# untitled.net
KiCad netlist of a schematic drawn in EAGLE
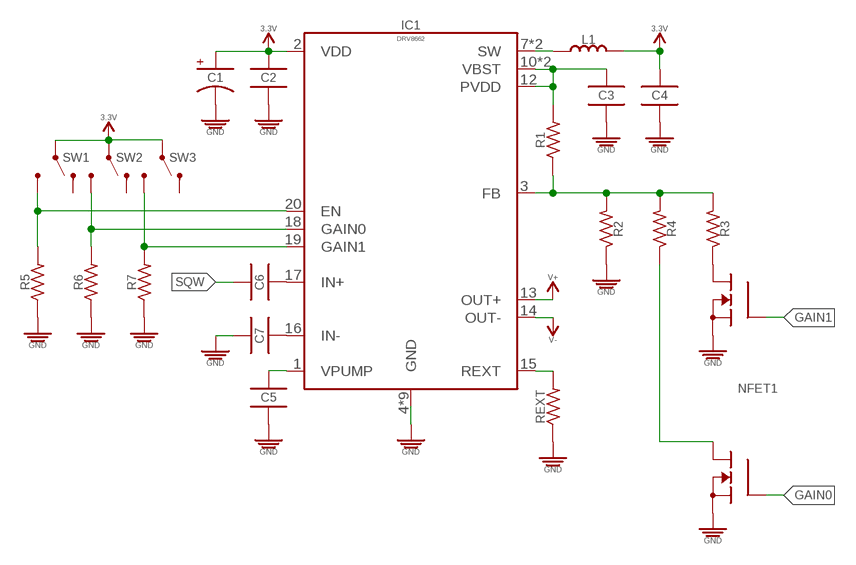
[diagram p0: schematic, sheet 1]

(export (version "E")
  (design (tool "Eeschema 10.0.6"))
  (components
    (comp (ref "C1")
      (value "100uF/10V")
      (footprint "eagle-import:CAPCP3216X160")
      (fields (field (name "MFR") "AVX Corporation") (field (name "MPN") "TLJA107M010R1400"))
      (libsource (lib "eagle-import") (part "100UF-POLARIZED_TANT_SMD-1206_10V-20%"))
    )
    (comp (ref "C2")
      (value "0.1uF/50V")
      (footprint "eagle-import:CAPC1005X55_SMD-0402")
      (fields (field (name "MFR") "TDK Corporation") (field (name "MPN") "C1005X7R1H104K050BE"))
      (libsource (lib "eagle-import") (part "0.1UF_SMD-0402_50V-10%"))
    )
    (comp (ref "C3")
      (value "0.1uF/250V/0805")
      (footprint "eagle-import:CAPC2012X95_SMD-0805")
      (fields (field (name "MFR") "TDK Corporation") (field (name "MPN") "C2012X7T2E104M125AE"))
      (libsource (lib "eagle-import") (part "0.1UF_SMD-0805_250V-10%"))
    )
    (comp (ref "C4")
      (value "0.1uF/50V")
      (footprint "eagle-import:CAPC1608X95")
      (fields (field (name "MFR") "TDK Corporation") (field (name "MPN") "CGA3E3X8R1H104K080AB"))
      (libsource (lib "eagle-import") (part "0.1UF_SMD-0603_50V-20%"))
    )
    (comp (ref "C5")
      (value "0.1uF/50V")
      (footprint "eagle-import:CAPC1005X55_SMD-0402")
      (fields (field (name "MFR") "TDK Corporation") (field (name "MPN") "C1005X7R1H104K050BE"))
      (libsource (lib "eagle-import") (part "0.1UF_SMD-0402_50V-10%"))
    )
    (comp (ref "C6")
      (value "0.1uF/50V")
      (footprint "eagle-import:CAPC1005X55_SMD-0402")
      (fields (field (name "MFR") "TDK Corporation") (field (name "MPN") "C1005X7R1H104K050BE"))
      (libsource (lib "eagle-import") (part "0.1UF_SMD-0402_50V-10%"))
    )
    (comp (ref "C7")
      (value "0.1uF/50V")
      (footprint "eagle-import:CAPC1005X55_SMD-0402")
      (fields (field (name "MFR") "TDK Corporation") (field (name "MPN") "C1005X7R1H104K050BE"))
      (libsource (lib "eagle-import") (part "0.1UF_SMD-0402_50V-10%"))
    )
    (comp (ref "IC1")
      (value "DRV8662")
      (footprint "eagle-import:QFN50P400X400X100-21T270")
      (fields (field (name "MFR") "Texas Instruments") (field (name "MPN") "DRV8662RGPR"))
      (libsource (lib "eagle-import") (part "DRV8662_PIEZO_HAPTICS_DRIVER_QFN-20-EP"))
    )
    (comp (ref "L1")
      (value "4.7uH/2A/1008")
      (footprint "eagle-import:INDC2520X100")
      (fields
        (field (name "MFR") "Murata Electronics North America")
        (field (name "MPN") "DFE252012P-4R7M=P2")
      )
      (libsource (lib "eagle-import") (part "4.7UH_SMD-1008_2A-0.200OHM-20%"))
    )
    (comp (ref "NFET1")
      (value "2N7002DW")
      (footprint "eagle-import:SOT65P230X110-6")
      (fields (field (name "MFR") "Micro Commercial Co") (field (name "MPN") "2N7002DW-TP"))
      (libsource (lib "eagle-import") (part "MOSFET_N-CHANNEL_2-ARRAY_2N7002DW_115MA-60V"))
    )
    (comp (ref "R1")
      (value "768K")
      (footprint "eagle-import:RESC1005X35_SMD-0402")
      (fields (field (name "MFR") "Yageo") (field (name "MPN") "RC0402FR-07768KL"))
      (libsource (lib "eagle-import") (part "768KΩ_SMD-0402_1/16W-1%"))
    )
    (comp (ref "R2")
      (value "115K")
      (footprint "eagle-import:RESC1005X35_SMD-0402")
      (fields (field (name "MFR") "Yageo") (field (name "MPN") "RC0402FR-0735K7L"))
      (libsource (lib "eagle-import") (part "35.7KΩ_SMD-0402_1/16W-1%"))
    )
    (comp (ref "R3")
      (value "220K")
      (footprint "eagle-import:RESC1005X35_SMD-0402")
      (fields (field (name "MFR") "Yageo") (field (name "MPN") "RC0402FR-0720KL"))
      (libsource (lib "eagle-import") (part "20KΩ_SMD-0402_1/16W-1%"))
    )
    (comp (ref "R4")
      (value "100K")
      (footprint "eagle-import:RESC1005X35_SMD-0402")
      (fields (field (name "MFR") "Yageo") (field (name "MPN") "RC0402FR-0741K2L"))
      (libsource (lib "eagle-import") (part "41.2KΩ_SMD-0402_1/16W-1%"))
    )
    (comp (ref "R5")
      (value "10K")
      (footprint "eagle-import:RESC1005X35_SMD-0402")
      (fields (field (name "MFR") "Yageo") (field (name "MPN") "RC0402JR-0710KP"))
      (libsource (lib "eagle-import") (part "10KΩ_SMD-0402_1/16W-5%"))
    )
    (comp (ref "R6")
      (value "10K")
      (footprint "eagle-import:RESC1005X35_SMD-0402")
      (fields (field (name "MFR") "Yageo") (field (name "MPN") "RC0402JR-0710KP"))
      (libsource (lib "eagle-import") (part "10KΩ_SMD-0402_1/16W-5%"))
    )
    (comp (ref "R7")
      (value "10K")
      (footprint "eagle-import:RESC1005X35_SMD-0402")
      (fields (field (name "MFR") "Yageo") (field (name "MPN") "RC0402JR-0710KP"))
      (libsource (lib "eagle-import") (part "10KΩ_SMD-0402_1/16W-5%"))
    )
    (comp (ref "REXT")
      (value "7.5K")
      (footprint "eagle-import:RESC1005X35_SMD-0402")
      (fields (field (name "MFR") "Yageo") (field (name "MPN") "RC0402FR-077K5L"))
      (libsource (lib "eagle-import") (part "7.5KΩ_SMD-0402_1/16W-1%"))
    )
    (comp (ref "SW1")
      (value "300mA/4V")
      (footprint "eagle-import:SW_SLIDE_SPDT_RA_SMD_4V_300MA_6.7L-2.6W")
      (fields
        (field (name "MFR") "APEM Inc.")
        (field (name "MPN") "MA12RTR")
        (field (name "CREATOR") "MrSwirlyEyes")
      )
      (libsource (lib "eagle-import") (part "SWITCH_SPDT_RA_SMD_300MA-4V_6.7L-2.6W"))
    )
    (comp (ref "SW2")
      (value "300mA/4V")
      (footprint "eagle-import:SW_SLIDE_SPDT_RA_SMD_4V_300MA_6.7L-2.6W")
      (fields
        (field (name "MFR") "APEM Inc.")
        (field (name "MPN") "MA12RTR")
        (field (name "CREATOR") "MrSwirlyEyes")
      )
      (libsource (lib "eagle-import") (part "SWITCH_SPDT_RA_SMD_300MA-4V_6.7L-2.6W"))
    )
    (comp (ref "SW3")
      (value "300mA/4V")
      (footprint "eagle-import:SW_SLIDE_SPDT_RA_SMD_4V_300MA_6.7L-2.6W")
      (fields
        (field (name "MFR") "APEM Inc.")
        (field (name "MPN") "MA12RTR")
        (field (name "CREATOR") "MrSwirlyEyes")
      )
      (libsource (lib "eagle-import") (part "SWITCH_SPDT_RA_SMD_300MA-4V_6.7L-2.6W"))
    )
  )
  (nets
    (net (code "1") (name "3.3V") (class "Default")
      (node (ref "C1") (pin "A") (pinfunction "A_A") (pintype "passive"))
      (node (ref "C2") (pin "1") (pinfunction "1_1") (pintype "passive"))
      (node (ref "C4") (pin "1") (pinfunction "1_1") (pintype "passive"))
      (node (ref "IC1") (pin "2") (pinfunction "VDD_2") (pintype "power_in"))
      (node (ref "L1") (pin "2") (pinfunction "2_2") (pintype "passive"))
      (node (ref "SW1") (pin "2") (pinfunction "P_2") (pintype "passive"))
      (node (ref "SW2") (pin "2") (pinfunction "P_2") (pintype "passive"))
      (node (ref "SW3") (pin "2") (pinfunction "P_2") (pintype "passive"))
    )
    (net (code "2") (name "GAIN0") (class "Default")
      (node (ref "IC1") (pin "18") (pinfunction "GAIN0_18") (pintype "input"))
      (node (ref "NFET1") (pin "5") (pinfunction "G2_5") (pintype "passive"))
      (node (ref "R6") (pin "2") (pinfunction "2_2") (pintype "passive"))
      (node (ref "SW2") (pin "3") (pinfunction "S2_3") (pintype "passive"))
    )
    (net (code "3") (name "GAIN1") (class "Default")
      (node (ref "IC1") (pin "19") (pinfunction "GAIN1_19") (pintype "input"))
      (node (ref "NFET1") (pin "2") (pinfunction "G1_2") (pintype "passive"))
      (node (ref "R7") (pin "2") (pinfunction "2_2") (pintype "passive"))
      (node (ref "SW3") (pin "3") (pinfunction "S2_3") (pintype "passive"))
    )
    (net (code "4") (name "GND") (class "Default")
      (node (ref "C1") (pin "K") (pinfunction "K_K") (pintype "passive"))
      (node (ref "C2") (pin "2") (pinfunction "2_2") (pintype "passive"))
      (node (ref "C3") (pin "2") (pinfunction "2_2") (pintype "passive"))
      (node (ref "C4") (pin "2") (pinfunction "2_2") (pintype "passive"))
      (node (ref "C5") (pin "2") (pinfunction "2_2") (pintype "passive"))
      (node (ref "C7") (pin "1") (pinfunction "1_1") (pintype "passive"))
      (node (ref "IC1") (pin "4") (pinfunction "GND_4") (pintype "power_in"))
      (node (ref "IC1") (pin "5") (pinfunction "GND_5") (pintype "power_in"))
      (node (ref "IC1") (pin "6") (pinfunction "GND_6") (pintype "power_in"))
      (node (ref "IC1") (pin "9") (pinfunction "GND_9") (pintype "power_in"))
      (node (ref "IC1") (pin "EP") (pinfunction "GND_EP") (pintype "power_in"))
      (node (ref "IC1") (pin "P$1") (pinfunction "GND_P$1") (pintype "power_in"))
      (node (ref "IC1") (pin "P$2") (pinfunction "GND_P$2") (pintype "power_in"))
      (node (ref "IC1") (pin "P$3") (pinfunction "GND_P$3") (pintype "power_in"))
      (node (ref "IC1") (pin "P$4") (pinfunction "GND_P$4") (pintype "power_in"))
      (node (ref "NFET1") (pin "1") (pinfunction "S1_1") (pintype "passive"))
      (node (ref "NFET1") (pin "4") (pinfunction "S2_4") (pintype "passive"))
      (node (ref "R2") (pin "1") (pinfunction "1_1") (pintype "passive"))
      (node (ref "R5") (pin "1") (pinfunction "1_1") (pintype "passive"))
      (node (ref "R6") (pin "1") (pinfunction "1_1") (pintype "passive"))
      (node (ref "R7") (pin "1") (pinfunction "1_1") (pintype "passive"))
      (node (ref "REXT") (pin "1") (pinfunction "1_1") (pintype "passive"))
    )
    (net (code "5") (name "Net-(IC1-EN)") (class "Default")
      (node (ref "IC1") (pin "20") (pinfunction "EN_20") (pintype "input"))
      (node (ref "R5") (pin "2") (pinfunction "2_2") (pintype "passive"))
      (node (ref "SW1") (pin "3") (pinfunction "S2_3") (pintype "passive"))
    )
    (net (code "6") (name "Net-(IC1-FB)") (class "Default")
      (node (ref "IC1") (pin "3") (pinfunction "FB_3") (pintype "input"))
      (node (ref "R1") (pin "1") (pinfunction "1_1") (pintype "passive"))
      (node (ref "R2") (pin "2") (pinfunction "2_2") (pintype "passive"))
      (node (ref "R3") (pin "2") (pinfunction "2_2") (pintype "passive"))
      (node (ref "R4") (pin "2") (pinfunction "2_2") (pintype "passive"))
    )
    (net (code "7") (name "Net-(IC1-IN+)") (class "Default")
      (node (ref "C6") (pin "2") (pinfunction "2_2") (pintype "passive"))
      (node (ref "IC1") (pin "17") (pinfunction "IN+_17") (pintype "input"))
    )
    (net (code "8") (name "Net-(IC1-IN-)") (class "Default")
      (node (ref "C7") (pin "2") (pinfunction "2_2") (pintype "passive"))
      (node (ref "IC1") (pin "16") (pinfunction "IN-_16") (pintype "input"))
    )
    (net (code "9") (name "Net-(IC1-PVDD)") (class "Default")
      (node (ref "C3") (pin "1") (pinfunction "1_1") (pintype "passive"))
      (node (ref "IC1") (pin "10") (pinfunction "VBST_10") (pintype "power_in"))
      (node (ref "IC1") (pin "11") (pinfunction "VBST_11") (pintype "power_in"))
      (node (ref "IC1") (pin "12") (pinfunction "PVDD_12") (pintype "power_in"))
      (node (ref "R1") (pin "2") (pinfunction "2_2") (pintype "passive"))
    )
    (net (code "10") (name "Net-(IC1-REXT)") (class "Default")
      (node (ref "IC1") (pin "15") (pinfunction "REXT_15") (pintype "input"))
      (node (ref "REXT") (pin "2") (pinfunction "2_2") (pintype "passive"))
    )
    (net (code "11") (name "Net-(IC1-SW-Pad7)") (class "Default")
      (node (ref "IC1") (pin "7") (pinfunction "SW_7") (pintype "power_in"))
      (node (ref "IC1") (pin "8") (pinfunction "SW_8") (pintype "power_in"))
      (node (ref "L1") (pin "1") (pinfunction "1_1") (pintype "passive"))
    )
    (net (code "12") (name "Net-(IC1-VPUMP)") (class "Default")
      (node (ref "C5") (pin "1") (pinfunction "1_1") (pintype "passive"))
      (node (ref "IC1") (pin "1") (pinfunction "VPUMP_1") (pintype "power_in"))
    )
    (net (code "13") (name "Net-(NFET1-D1)") (class "Default")
      (node (ref "NFET1") (pin "6") (pinfunction "D1_6") (pintype "passive"))
      (node (ref "R3") (pin "1") (pinfunction "1_1") (pintype "passive"))
    )
    (net (code "14") (name "Net-(NFET1-D2)") (class "Default")
      (node (ref "NFET1") (pin "3") (pinfunction "D2_3") (pintype "passive"))
      (node (ref "R4") (pin "1") (pinfunction "1_1") (pintype "passive"))
    )
    (net (code "15") (name "SQW") (class "Default")
      (node (ref "C6") (pin "1") (pinfunction "1_1") (pintype "passive"))
    )
    (net (code "16") (name "V+") (class "Default")
      (node (ref "IC1") (pin "13") (pinfunction "OUT+_13") (pintype "output"))
    )
    (net (code "17") (name "V-") (class "Default")
      (node (ref "IC1") (pin "14") (pinfunction "OUT-_14") (pintype "output"))
    )
    (net (code "18") (name "unconnected-(SW1-S1-Pad1)") (class "Default")
      (node (ref "SW1") (pin "1") (pinfunction "S1_1") (pintype "passive"))
    )
    (net (code "19") (name "unconnected-(SW2-S1-Pad1)") (class "Default")
      (node (ref "SW2") (pin "1") (pinfunction "S1_1") (pintype "passive"))
    )
    (net (code "20") (name "unconnected-(SW3-S1-Pad1)") (class "Default")
      (node (ref "SW3") (pin "1") (pinfunction "S1_1") (pintype "passive"))
    )
  )
)
